# AFM_Power_board.net
KiCad netlist of a schematic drawn in EAGLE
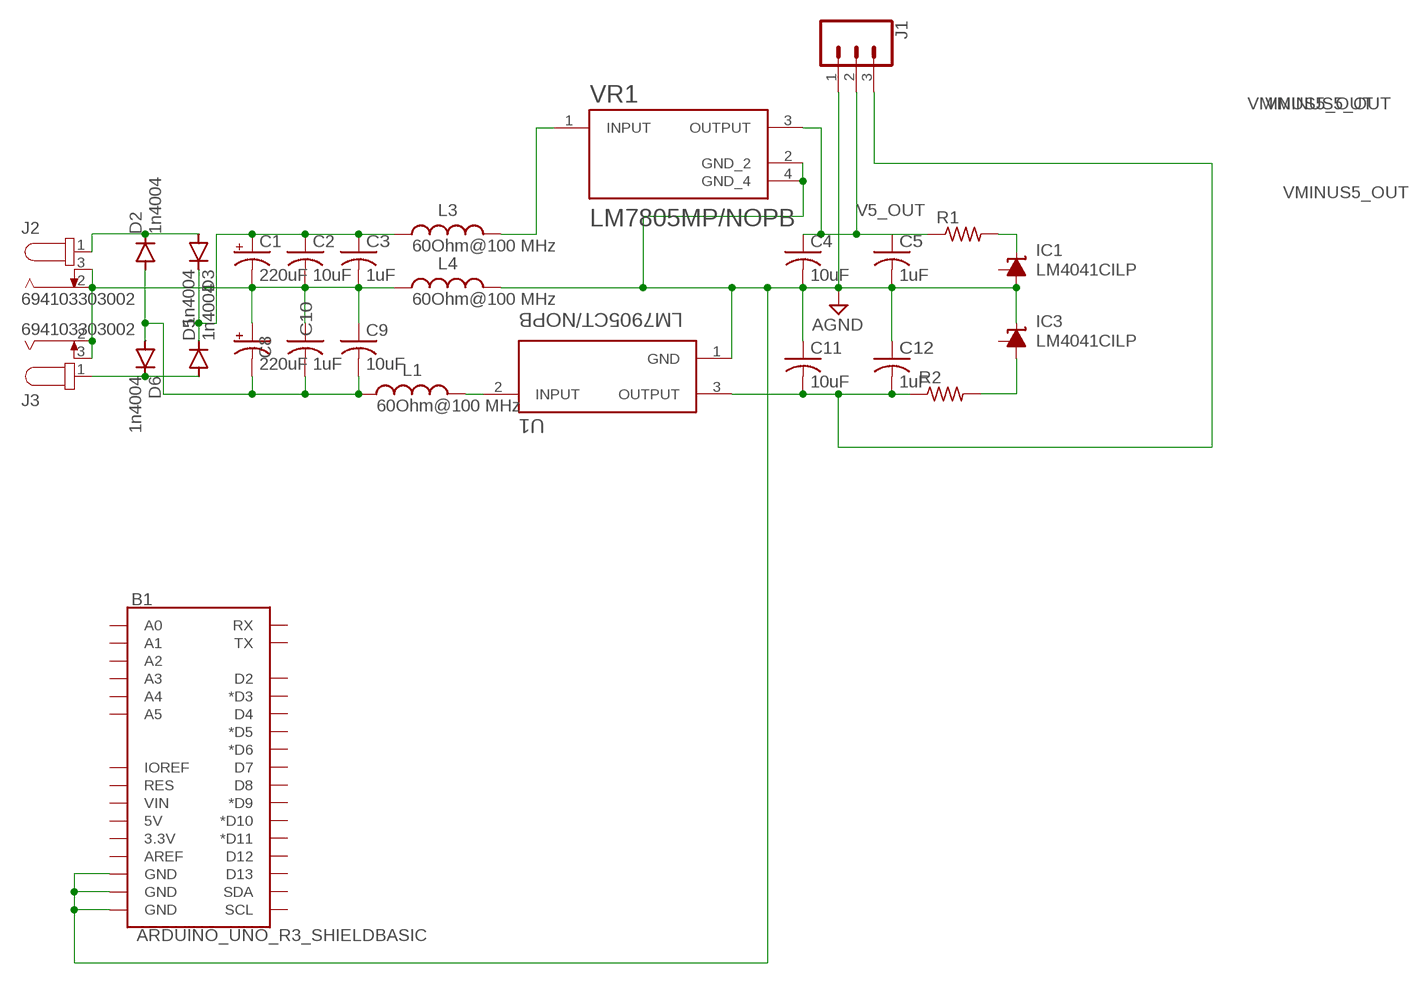
[diagram p0: schematic, sheet 1]

(export (version "E")
  (design (tool "Eeschema 10.0.6"))
  (components
    (comp (ref "B1")
      (value "ARDUINO_UNO_R3_SHIELDBASIC")
      (footprint "eagle-import:UNO_R3_SHIELD")
      (libsource (lib "eagle-import") (part "ARDUINO_UNO_R3_SHIELDBASIC"))
    )
    (comp (ref "C1")
      (value "220uF")
      (footprint "eagle-import:E5-8,5")
      (libsource (lib "eagle-import") (part "CAPACITOR-PE5-8.5"))
    )
    (comp (ref "C2")
      (value "10uF")
      (footprint "eagle-import:C050-024X044")
      (libsource (lib "eagle-import") (part "C-US050-024X044"))
    )
    (comp (ref "C3")
      (value "1uF")
      (footprint "eagle-import:C050-024X044")
      (libsource (lib "eagle-import") (part "C-US050-024X044"))
    )
    (comp (ref "C4")
      (value "10uF")
      (footprint "eagle-import:C050-024X044")
      (libsource (lib "eagle-import") (part "C-US050-024X044"))
    )
    (comp (ref "C5")
      (value "1uF")
      (footprint "eagle-import:C050-024X044")
      (libsource (lib "eagle-import") (part "C-US050-024X044"))
    )
    (comp (ref "C8")
      (value "220uF")
      (footprint "eagle-import:E5-8,5")
      (libsource (lib "eagle-import") (part "CAPACITOR-PE5-8.5"))
    )
    (comp (ref "C9")
      (value "10uF")
      (footprint "eagle-import:C050-024X044")
      (libsource (lib "eagle-import") (part "C-US050-024X044"))
    )
    (comp (ref "C10")
      (value "1uF")
      (footprint "eagle-import:C050-024X044")
      (libsource (lib "eagle-import") (part "C-US050-024X044"))
    )
    (comp (ref "C11")
      (value "10uF")
      (footprint "eagle-import:C050-024X044")
      (libsource (lib "eagle-import") (part "C-US050-024X044"))
    )
    (comp (ref "C12")
      (value "1uF")
      (footprint "eagle-import:C050-024X044")
      (libsource (lib "eagle-import") (part "C-US050-024X044"))
    )
    (comp (ref "D2")
      (value "1n4004")
      (footprint "eagle-import:SOD123")
      (libsource (lib "eagle-import") (part "DIODE-SOD123"))
    )
    (comp (ref "D3")
      (value "1n4004")
      (footprint "eagle-import:SOD123")
      (libsource (lib "eagle-import") (part "DIODE-SOD123"))
    )
    (comp (ref "D5")
      (value "1n4004")
      (footprint "eagle-import:SOD123")
      (libsource (lib "eagle-import") (part "DIODE-SOD123"))
    )
    (comp (ref "D6")
      (value "1n4004")
      (footprint "eagle-import:SOD123")
      (libsource (lib "eagle-import") (part "DIODE-SOD123"))
    )
    (comp (ref "IC1")
      (value "LM4041CILP")
      (footprint "eagle-import:LP_O-PBCY-W3")
      (libsource (lib "eagle-import") (part "LM4041ILPC"))
    )
    (comp (ref "IC3")
      (value "LM4041CILP")
      (footprint "eagle-import:LP_O-PBCY-W3")
      (libsource (lib "eagle-import") (part "LM4041ILPC"))
    )
    (comp (ref "J1")
      (value "CONN_03LONGPADS")
      (footprint "eagle-import:1X03_LONGPADS")
      (libsource (lib "eagle-import") (part "CONN_03LONGPADS"))
    )
    (comp (ref "J2")
      (value "694103303002")
      (footprint "eagle-import:694103303002")
      (fields
        (field (name "DIGIKEY_PART_NUMBER") "732-5925-ND")
        (field (name "MANUFACTURER") "Wurth Electronics Inc.")
        (field (name "CREATED_BY") "PCBLayout.com")
      )
      (libsource (lib "eagle-import") (part "694103303002"))
    )
    (comp (ref "J3")
      (value "694103303002")
      (footprint "eagle-import:694103303002")
      (fields
        (field (name "DIGIKEY_PART_NUMBER") "732-5925-ND")
        (field (name "MANUFACTURER") "Wurth Electronics Inc.")
        (field (name "CREATED_BY") "PCBLayout.com")
      )
      (libsource (lib "eagle-import") (part "694103303002"))
    )
    (comp (ref "L1")
      (value "60Ohm@100 MHz")
      (footprint "eagle-import:WE-CBF_0603_W2.2")
      (libsource (lib "eagle-import") (part "WE-CBF_0603_WB_HS_74279267"))
    )
    (comp (ref "L3")
      (value "60Ohm@100 MHz")
      (footprint "eagle-import:WE-CBF_0603_W2.2")
      (libsource (lib "eagle-import") (part "WE-CBF_0603_WB_HS_74279267"))
    )
    (comp (ref "L4")
      (value "60Ohm@100 MHz")
      (footprint "eagle-import:WE-CBF_0603_W2.2")
      (libsource (lib "eagle-import") (part "WE-CBF_0603_WB_HS_74279267"))
    )
    (comp (ref "R1")
      (value "R-US_0204/5")
      (footprint "eagle-import:0204_5")
      (libsource (lib "eagle-import") (part "R-US_0204/5"))
    )
    (comp (ref "R2")
      (value "R-US_0204/5")
      (footprint "eagle-import:0204_5")
      (libsource (lib "eagle-import") (part "R-US_0204/5"))
    )
    (comp (ref "U1")
      (value "LM7905CT/NOPB")
      (footprint "eagle-import:TO254P1016X4575X1955-3")
      (fields (field (name "MF") "Texas Instruments"))
      (libsource (lib "eagle-import") (part "LM7905CT/NOPB"))
    )
    (comp (ref "VR1")
      (value "LM7805MP/NOPB")
      (footprint "eagle-import:VREG_LM7805MP_NOPB")
      (fields (field (name "MF") "Texas Instruments"))
      (libsource (lib "eagle-import") (part "LM7805MP/NOPB"))
    )
  )
  (nets
    (net (code "1") (name "/V5_OUT") (class "Default")
      (node (ref "C4") (pin "1") (pinfunction "1_1") (pintype "passive"))
      (node (ref "C5") (pin "1") (pinfunction "1_1") (pintype "passive"))
      (node (ref "J1") (pin "2") (pinfunction "2_2") (pintype "passive"))
      (node (ref "R1") (pin "1") (pinfunction "1_1") (pintype "passive"))
      (node (ref "VR1") (pin "3") (pinfunction "OUTPUT_3") (pintype "output"))
    )
    (net (code "2") (name "/VMINUS5_OUT") (class "Default")
      (node (ref "C11") (pin "2") (pinfunction "2_2") (pintype "passive"))
      (node (ref "C12") (pin "2") (pinfunction "2_2") (pintype "passive"))
      (node (ref "J1") (pin "3") (pinfunction "3_3") (pintype "passive"))
      (node (ref "R2") (pin "1") (pinfunction "1_1") (pintype "passive"))
      (node (ref "U1") (pin "3") (pinfunction "OUTPUT_3") (pintype "output"))
    )
    (net (code "3") (name "AGND") (class "Default")
      (node (ref "B1") (pin "GND@0") (pinfunction "GND_GND@0") (pintype "bidirectional"))
      (node (ref "B1") (pin "GND@1") (pinfunction "GND_GND@1") (pintype "bidirectional"))
      (node (ref "B1") (pin "GND@2") (pinfunction "GND_GND@2") (pintype "bidirectional"))
      (node (ref "C11") (pin "1") (pinfunction "1_1") (pintype "passive"))
      (node (ref "C12") (pin "1") (pinfunction "1_1") (pintype "passive"))
      (node (ref "C4") (pin "2") (pinfunction "2_2") (pintype "passive"))
      (node (ref "C5") (pin "2") (pinfunction "2_2") (pintype "passive"))
      (node (ref "IC1") (pin "3") (pinfunction "A_3") (pintype "passive"))
      (node (ref "IC3") (pin "2") (pinfunction "C_2") (pintype "passive"))
      (node (ref "J1") (pin "1") (pinfunction "1_1") (pintype "passive"))
      (node (ref "L4") (pin "2") (pinfunction "2_2") (pintype "passive"))
      (node (ref "U1") (pin "1") (pinfunction "GND_1") (pintype "power_in"))
      (node (ref "VR1") (pin "2") (pinfunction "GND_2_2") (pintype "power_in"))
      (node (ref "VR1") (pin "4") (pinfunction "GND_4_4") (pintype "power_in"))
    )
    (net (code "4") (name "Net-(C1-Pad+)") (class "Default")
      (node (ref "C1") (pin "+") (pinfunction "+_+") (pintype "passive"))
      (node (ref "C2") (pin "1") (pinfunction "1_1") (pintype "passive"))
      (node (ref "C3") (pin "1") (pinfunction "1_1") (pintype "passive"))
      (node (ref "D3") (pin "C") (pinfunction "C_C") (pintype "passive"))
      (node (ref "D5") (pin "C") (pinfunction "C_C") (pintype "passive"))
      (node (ref "L3") (pin "1") (pinfunction "1_1") (pintype "passive"))
    )
    (net (code "5") (name "Net-(C1-Pad-)") (class "Default")
      (node (ref "C1") (pin "-") (pinfunction "-_-") (pintype "passive"))
      (node (ref "C10") (pin "1") (pinfunction "1_1") (pintype "passive"))
      (node (ref "C2") (pin "2") (pinfunction "2_2") (pintype "passive"))
      (node (ref "C3") (pin "2") (pinfunction "2_2") (pintype "passive"))
      (node (ref "C8") (pin "+") (pinfunction "+_+") (pintype "passive"))
      (node (ref "C9") (pin "1") (pinfunction "1_1") (pintype "passive"))
      (node (ref "J2") (pin "2") (pinfunction "2_2") (pintype "passive"))
      (node (ref "J2") (pin "3") (pinfunction "3_3") (pintype "passive"))
      (node (ref "J3") (pin "2") (pinfunction "2_2") (pintype "passive"))
      (node (ref "J3") (pin "3") (pinfunction "3_3") (pintype "passive"))
      (node (ref "L4") (pin "1") (pinfunction "1_1") (pintype "passive"))
    )
    (net (code "6") (name "Net-(C10-Pad2)") (class "Default")
      (node (ref "C10") (pin "2") (pinfunction "2_2") (pintype "passive"))
      (node (ref "C8") (pin "-") (pinfunction "-_-") (pintype "passive"))
      (node (ref "C9") (pin "2") (pinfunction "2_2") (pintype "passive"))
      (node (ref "D2") (pin "A") (pinfunction "A_A") (pintype "passive"))
      (node (ref "D6") (pin "A") (pinfunction "A_A") (pintype "passive"))
      (node (ref "L1") (pin "1") (pinfunction "1_1") (pintype "passive"))
    )
    (net (code "7") (name "Net-(D2-PadC)") (class "Default")
      (node (ref "D2") (pin "C") (pinfunction "C_C") (pintype "passive"))
      (node (ref "D3") (pin "A") (pinfunction "A_A") (pintype "passive"))
      (node (ref "J2") (pin "1") (pinfunction "1_1") (pintype "passive"))
    )
    (net (code "8") (name "Net-(D5-PadA)") (class "Default")
      (node (ref "D5") (pin "A") (pinfunction "A_A") (pintype "passive"))
      (node (ref "D6") (pin "C") (pinfunction "C_C") (pintype "passive"))
      (node (ref "J3") (pin "1") (pinfunction "1_1") (pintype "passive"))
    )
    (net (code "9") (name "Net-(IC1-C)") (class "Default")
      (node (ref "IC1") (pin "2") (pinfunction "C_2") (pintype "passive"))
      (node (ref "R1") (pin "2") (pinfunction "2_2") (pintype "passive"))
    )
    (net (code "10") (name "Net-(IC3-A)") (class "Default")
      (node (ref "IC3") (pin "3") (pinfunction "A_3") (pintype "passive"))
      (node (ref "R2") (pin "2") (pinfunction "2_2") (pintype "passive"))
    )
    (net (code "11") (name "Net-(U1-INPUT)") (class "Default")
      (node (ref "L1") (pin "2") (pinfunction "2_2") (pintype "passive"))
      (node (ref "U1") (pin "2") (pinfunction "INPUT_2") (pintype "input"))
    )
    (net (code "12") (name "Net-(VR1-INPUT)") (class "Default")
      (node (ref "L3") (pin "2") (pinfunction "2_2") (pintype "passive"))
      (node (ref "VR1") (pin "1") (pinfunction "INPUT_1") (pintype "input"))
    )
    (net (code "13") (name "unconnected-(B1-*D3-PadD3)") (class "Default")
      (node (ref "B1") (pin "D3") (pinfunction "*D3_D3") (pintype "bidirectional"))
    )
    (net (code "14") (name "unconnected-(B1-*D5-PadD5)") (class "Default")
      (node (ref "B1") (pin "D5") (pinfunction "*D5_D5") (pintype "bidirectional"))
    )
    (net (code "15") (name "unconnected-(B1-*D6-PadD6)") (class "Default")
      (node (ref "B1") (pin "D6") (pinfunction "*D6_D6") (pintype "bidirectional"))
    )
    (net (code "16") (name "unconnected-(B1-*D9-PadD9)") (class "Default")
      (node (ref "B1") (pin "D9") (pinfunction "*D9_D9") (pintype "bidirectional"))
    )
    (net (code "17") (name "unconnected-(B1-*D10-PadD10)") (class "Default")
      (node (ref "B1") (pin "D10") (pinfunction "*D10_D10") (pintype "bidirectional"))
    )
    (net (code "18") (name "unconnected-(B1-*D11-PadD11)") (class "Default")
      (node (ref "B1") (pin "D11") (pinfunction "*D11_D11") (pintype "bidirectional"))
    )
    (net (code "19") (name "unconnected-(B1-Pad3.3V)") (class "Default")
      (node (ref "B1") (pin "3.3V") (pinfunction "3.3V_3.3V") (pintype "bidirectional"))
    )
    (net (code "20") (name "unconnected-(B1-Pad5V)") (class "Default")
      (node (ref "B1") (pin "5V") (pinfunction "5V_5V") (pintype "bidirectional"))
    )
    (net (code "21") (name "unconnected-(B1-PadA0)") (class "Default")
      (node (ref "B1") (pin "A0") (pinfunction "A0_A0") (pintype "bidirectional"))
    )
    (net (code "22") (name "unconnected-(B1-PadA1)") (class "Default")
      (node (ref "B1") (pin "A1") (pinfunction "A1_A1") (pintype "bidirectional"))
    )
    (net (code "23") (name "unconnected-(B1-PadA2)") (class "Default")
      (node (ref "B1") (pin "A2") (pinfunction "A2_A2") (pintype "bidirectional"))
    )
    (net (code "24") (name "unconnected-(B1-PadA3)") (class "Default")
      (node (ref "B1") (pin "A3") (pinfunction "A3_A3") (pintype "bidirectional"))
    )
    (net (code "25") (name "unconnected-(B1-PadA4)") (class "Default")
      (node (ref "B1") (pin "A4") (pinfunction "A4_A4") (pintype "bidirectional"))
    )
    (net (code "26") (name "unconnected-(B1-PadA5)") (class "Default")
      (node (ref "B1") (pin "A5") (pinfunction "A5_A5") (pintype "bidirectional"))
    )
    (net (code "27") (name "unconnected-(B1-PadAREF)") (class "Default")
      (node (ref "B1") (pin "AREF") (pinfunction "AREF_AREF") (pintype "bidirectional"))
    )
    (net (code "28") (name "unconnected-(B1-PadD2)") (class "Default")
      (node (ref "B1") (pin "D2") (pinfunction "D2_D2") (pintype "bidirectional"))
    )
    (net (code "29") (name "unconnected-(B1-PadD4)") (class "Default")
      (node (ref "B1") (pin "D4") (pinfunction "D4_D4") (pintype "bidirectional"))
    )
    (net (code "30") (name "unconnected-(B1-PadD7)") (class "Default")
      (node (ref "B1") (pin "D7") (pinfunction "D7_D7") (pintype "bidirectional"))
    )
    (net (code "31") (name "unconnected-(B1-PadD8)") (class "Default")
      (node (ref "B1") (pin "D8") (pinfunction "D8_D8") (pintype "bidirectional"))
    )
    (net (code "32") (name "unconnected-(B1-PadD12)") (class "Default")
      (node (ref "B1") (pin "D12") (pinfunction "D12_D12") (pintype "bidirectional"))
    )
    (net (code "33") (name "unconnected-(B1-PadD13)") (class "Default")
      (node (ref "B1") (pin "D13") (pinfunction "D13_D13") (pintype "bidirectional"))
    )
    (net (code "34") (name "unconnected-(B1-PadIOREF)") (class "Default")
      (node (ref "B1") (pin "IOREF") (pinfunction "IOREF_IOREF") (pintype "bidirectional"))
    )
    (net (code "35") (name "unconnected-(B1-PadRES)") (class "Default")
      (node (ref "B1") (pin "RES") (pinfunction "RES_RES") (pintype "bidirectional"))
    )
    (net (code "36") (name "unconnected-(B1-PadRX)") (class "Default")
      (node (ref "B1") (pin "RX") (pinfunction "RX_RX") (pintype "bidirectional"))
    )
    (net (code "37") (name "unconnected-(B1-PadSCL)") (class "Default")
      (node (ref "B1") (pin "SCL") (pinfunction "SCL_SCL") (pintype "bidirectional"))
    )
    (net (code "38") (name "unconnected-(B1-PadSDA)") (class "Default")
      (node (ref "B1") (pin "SDA") (pinfunction "SDA_SDA") (pintype "bidirectional"))
    )
    (net (code "39") (name "unconnected-(B1-PadTX)") (class "Default")
      (node (ref "B1") (pin "TX") (pinfunction "TX_TX") (pintype "bidirectional"))
    )
    (net (code "40") (name "unconnected-(B1-PadVIN)") (class "Default")
      (node (ref "B1") (pin "VIN") (pinfunction "VIN_VIN") (pintype "bidirectional"))
    )
    (net (code "41") (name "unconnected-(IC1-FB-Pad1)") (class "Default")
      (node (ref "IC1") (pin "1") (pinfunction "FB_1") (pintype "passive"))
    )
    (net (code "42") (name "unconnected-(IC3-FB-Pad1)") (class "Default")
      (node (ref "IC3") (pin "1") (pinfunction "FB_1") (pintype "passive"))
    )
  )
)
